# Part_M.net
KiCad netlist of a schematic drawn in Altium Designer
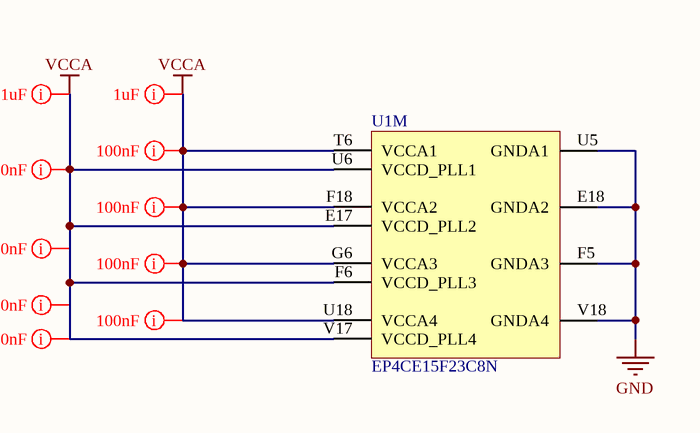
[diagram p0: Part M.SchDoc]

(export (version "E")
  (design (tool "Eeschema 10.0.6"))
  (components
    (comp (ref "U1")
      (value "EP4CE15F23C8N")
      (footprint "FBGA484_A-240")
      (fields (field (name "MANUFACTURER") "Altera"))
      (libsource (lib "Schlib1") (part "FPGA_EP4CE15F23C8N"))
    )
  )
  (nets
    (net (code "1") (name "GND") (class "Default")
      (node (ref "U1") (pin "E18") (pinfunction "GNDA2_E18") (pintype "power_in"))
      (node (ref "U1") (pin "F5") (pinfunction "GNDA3_F5") (pintype "power_in"))
      (node (ref "U1") (pin "U5") (pinfunction "GNDA1_U5") (pintype "power_in"))
      (node (ref "U1") (pin "V18") (pinfunction "GNDA4_V18") (pintype "power_in"))
    )
    (net (code "2") (name "VCCA") (class "Default")
      (node (ref "U1") (pin "E17") (pinfunction "VCCD_PLL2_E17") (pintype "power_in"))
      (node (ref "U1") (pin "F18") (pinfunction "VCCA2_F18") (pintype "power_in"))
      (node (ref "U1") (pin "F6") (pinfunction "VCCD_PLL3_F6") (pintype "power_in"))
      (node (ref "U1") (pin "G6") (pinfunction "VCCA3_G6") (pintype "power_in"))
      (node (ref "U1") (pin "T6") (pinfunction "VCCA1_T6") (pintype "power_in"))
      (node (ref "U1") (pin "U18") (pinfunction "VCCA4_U18") (pintype "power_in"))
      (node (ref "U1") (pin "U6") (pinfunction "VCCD_PLL1_U6") (pintype "power_in"))
      (node (ref "U1") (pin "V17") (pinfunction "VCCD_PLL4_V17") (pintype "power_in"))
    )
  )
)
